# ProPrj_DIR__2025-11-05.net
KiCad netlist of a schematic drawn in EasyEDA Pro
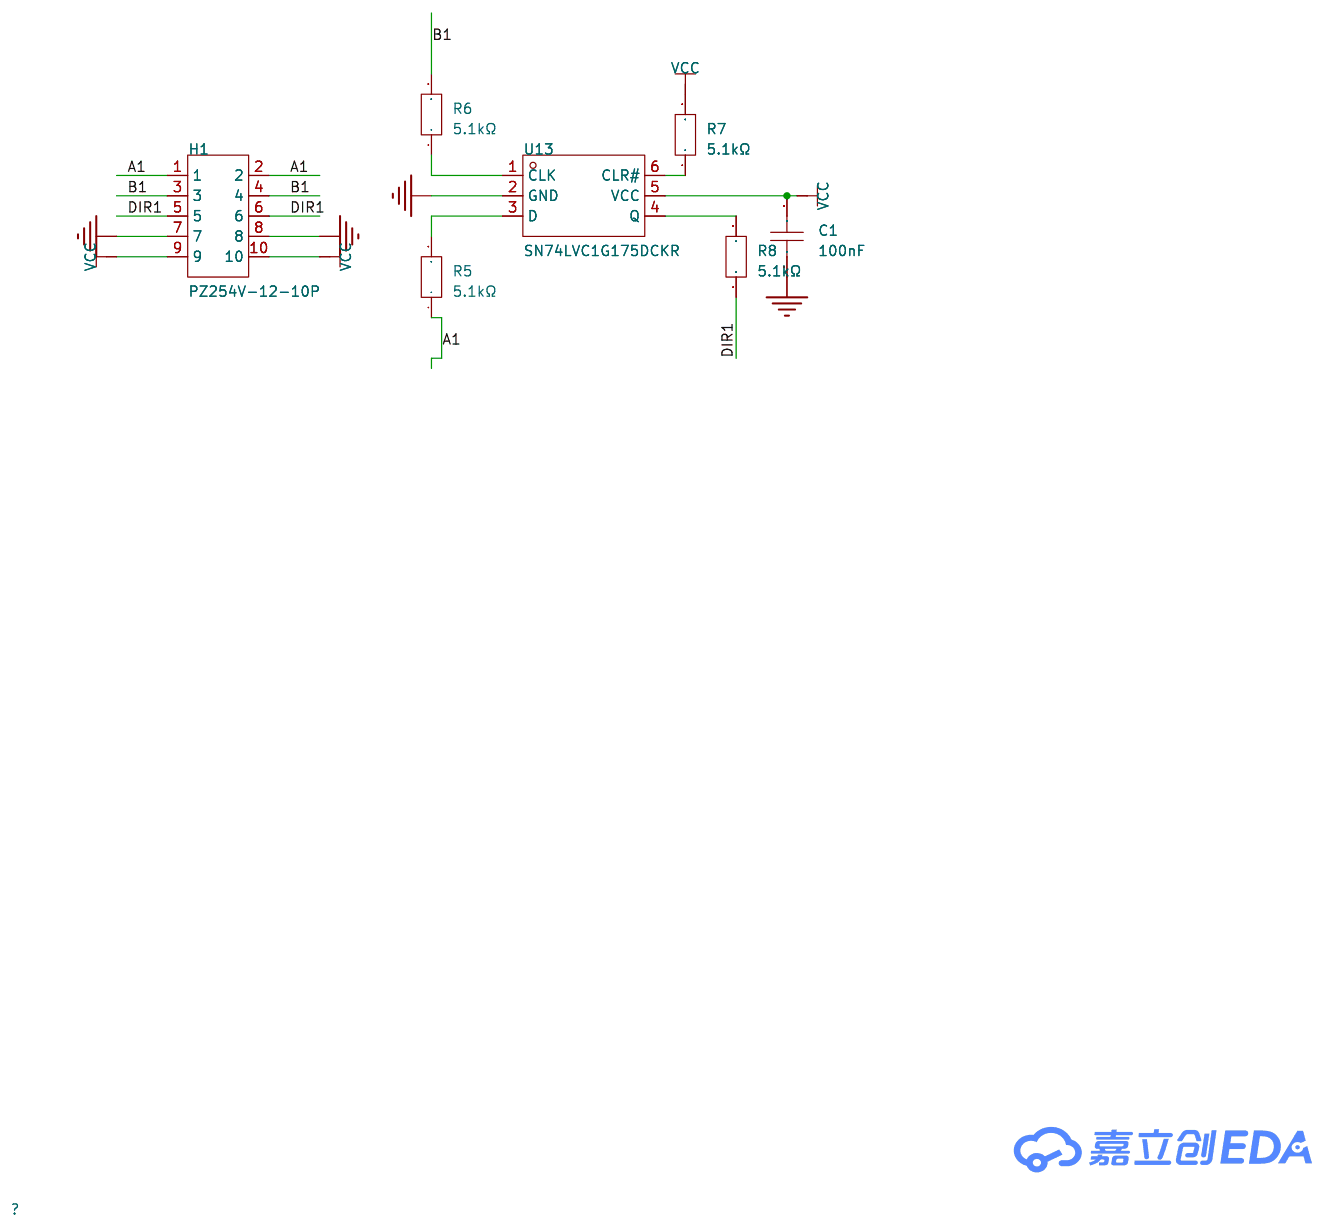
[diagram p0: schematic sheet]

(export (version "E")
  (design (tool "Eeschema 10.0.6"))
  (components
    (comp (ref "C1")
      (value "100nF")
      (footprint "easyedapro:C0603")
      (description "容值:100nF;精度:±10%;额定电压:50V;温度系数:X7R;")
      (fields
        (field (name "Manufacturer Part") "CC0603KRX7R9BB104")
        (field (name "Manufacturer") "YAGEO(国巨)")
      )
      (libsource (lib "easyedapro") (part "CC0603KRX7R9BB104"))
    )
    (comp (ref "H1")
      (value "PZ254V-12-10P")
      (footprint "easyedapro:HDR-TH_10P-P2.54-V-M-R2-C5-S2.54")
      (fields (field (name "Manufacturer") "XFCN(兴飞)"))
      (libsource (lib "easyedapro") (part "PZ254V-12-10P"))
    )
    (comp (ref "R5")
      (value "5.1kΩ")
      (footprint "easyedapro:R0603")
      (description "电阻类型:厚膜电阻;阻值:5.1kΩ;精度:±1%;功率:100mW;最大工作电压:75V;温度系数:±100ppm/°C;")
      (fields (field (name "Manufacturer Part") "FRC0603F5101TS") (field (name "Manufacturer") "FOJAN(富捷)"))
      (libsource (lib "easyedapro") (part "FRC0603F5101TS"))
    )
    (comp (ref "R6")
      (value "5.1kΩ")
      (footprint "easyedapro:R0603")
      (description "电阻类型:厚膜电阻;阻值:5.1kΩ;精度:±1%;功率:100mW;最大工作电压:75V;温度系数:±100ppm/°C;")
      (fields (field (name "Manufacturer Part") "FRC0603F5101TS") (field (name "Manufacturer") "FOJAN(富捷)"))
      (libsource (lib "easyedapro") (part "FRC0603F5101TS"))
    )
    (comp (ref "R7")
      (value "5.1kΩ")
      (footprint "easyedapro:R0603")
      (description "电阻类型:厚膜电阻;阻值:5.1kΩ;精度:±1%;功率:100mW;最大工作电压:75V;温度系数:±100ppm/°C;")
      (fields (field (name "Manufacturer Part") "FRC0603F5101TS") (field (name "Manufacturer") "FOJAN(富捷)"))
      (libsource (lib "easyedapro") (part "FRC0603F5101TS"))
    )
    (comp (ref "R8")
      (value "5.1kΩ")
      (footprint "easyedapro:R0603")
      (description "电阻类型:厚膜电阻;阻值:5.1kΩ;精度:±1%;功率:100mW;最大工作电压:75V;温度系数:±100ppm/°C;")
      (fields (field (name "Manufacturer Part") "FRC0603F5101TS") (field (name "Manufacturer") "FOJAN(富捷)"))
      (libsource (lib "easyedapro") (part "FRC0603F5101TS"))
    )
    (comp (ref "U13")
      (value "SN74LVC1G175DCKR")
      (footprint "easyedapro:SC-70-6_L2.0-W1.3-P0.65-LS2.1-BR")
      (description "类型:D-型;工作电压:1.65V~5.5V;时钟频率(fc):175MHz;元件数:1;每个元件位数:1;传播延迟(tpd):5ns@5V,50pF;静态电流(Iq):10uA;")
      (fields (field (name "Manufacturer") "TI(德州仪器)"))
      (libsource (lib "easyedapro") (part "SN74LVC1G175DCKR"))
    )
  )
  (nets
    (net (code "1") (name "/A1") (class "Default")
      (node (ref "H1") (pin "1") (pinfunction "1_1") (pintype "unspecified"))
      (node (ref "H1") (pin "2") (pinfunction "2_2") (pintype "unspecified"))
      (node (ref "R5") (pin "1") (pinfunction "1_1") (pintype "unspecified"))
    )
    (net (code "2") (name "/B1") (class "Default")
      (node (ref "H1") (pin "3") (pinfunction "3_3") (pintype "unspecified"))
      (node (ref "H1") (pin "4") (pinfunction "4_4") (pintype "unspecified"))
      (node (ref "R6") (pin "2") (pinfunction "2_2") (pintype "unspecified"))
    )
    (net (code "3") (name "/DIR1") (class "Default")
      (node (ref "H1") (pin "5") (pinfunction "5_5") (pintype "unspecified"))
      (node (ref "H1") (pin "6") (pinfunction "6_6") (pintype "unspecified"))
      (node (ref "R8") (pin "1") (pinfunction "1_1") (pintype "unspecified"))
    )
    (net (code "4") (name "GND") (class "Default")
      (node (ref "C1") (pin "1") (pinfunction "1_1") (pintype "unspecified"))
      (node (ref "H1") (pin "7") (pinfunction "7_7") (pintype "unspecified"))
      (node (ref "H1") (pin "8") (pinfunction "8_8") (pintype "unspecified"))
      (node (ref "U13") (pin "2") (pinfunction "GND_2") (pintype "unspecified"))
    )
    (net (code "5") (name "Net-(U13-CLK)") (class "Default")
      (node (ref "R6") (pin "1") (pinfunction "1_1") (pintype "unspecified"))
      (node (ref "U13") (pin "1") (pinfunction "CLK_1") (pintype "unspecified"))
    )
    (net (code "6") (name "Net-(U13-CLR#)") (class "Default")
      (node (ref "R7") (pin "1") (pinfunction "1_1") (pintype "unspecified"))
      (node (ref "U13") (pin "6") (pinfunction "CLR#_6") (pintype "unspecified"))
    )
    (net (code "7") (name "Net-(U13-D)") (class "Default")
      (node (ref "R5") (pin "2") (pinfunction "2_2") (pintype "unspecified"))
      (node (ref "U13") (pin "3") (pinfunction "D_3") (pintype "unspecified"))
    )
    (net (code "8") (name "Net-(U13-Q)") (class "Default")
      (node (ref "R8") (pin "2") (pinfunction "2_2") (pintype "unspecified"))
      (node (ref "U13") (pin "4") (pinfunction "Q_4") (pintype "unspecified"))
    )
    (net (code "9") (name "VCC") (class "Default")
      (node (ref "C1") (pin "2") (pinfunction "2_2") (pintype "unspecified"))
      (node (ref "H1") (pin "10") (pinfunction "10_10") (pintype "unspecified"))
      (node (ref "H1") (pin "9") (pinfunction "9_9") (pintype "unspecified"))
      (node (ref "R7") (pin "2") (pinfunction "2_2") (pintype "unspecified"))
      (node (ref "U13") (pin "5") (pinfunction "VCC_5") (pintype "unspecified"))
    )
  )
)
